# Power.net
KiCad netlist of a schematic drawn in Altium Designer
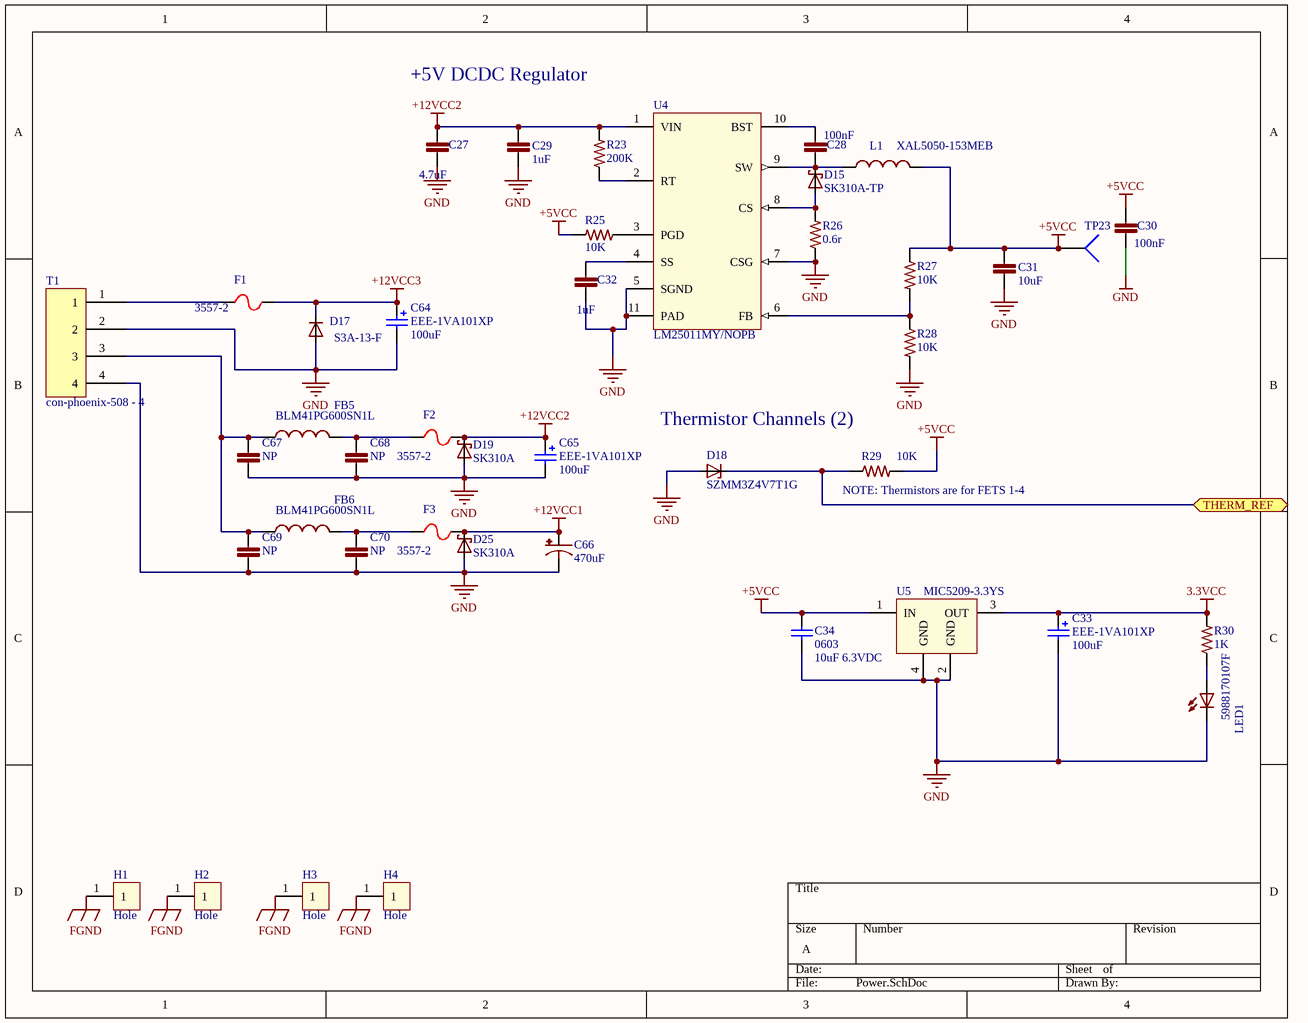
[diagram p0: Power.SchDoc]

(export (version "E")
  (design (tool "Eeschema 10.0.6"))
  (components
    (comp (ref "C27")
      (value "4.7uF")
      (footprint "C1206")
      (description "CAP CER 1206 4.7uF 50V 10% X5R")
      (fields
        (field (name "MANUFACTURERPARTNUMBER") "C1206C475K5PACTU")
        (field (name "PUBLISHER") "UltiMachine")
      )
      (libsource (lib "3Delight") (part "C1206C475K5PACTU"))
    )
    (comp (ref "C28")
      (value "100nF")
      (footprint "C0603")
      (description "CAP CER 0603 100nF 50V 10% X7R")
      (fields
        (field (name "MANUFACTURERPARTNUMBER") "C0603C104K5RACTU")
        (field (name "PUBLISHER") "UltiMachine")
      )
      (libsource (lib "3Delight") (part "C0603C104K5RACTU"))
    )
    (comp (ref "C29")
      (value "1uF")
      (footprint "C0805")
      (description "CAP CER 0805 1uF 50V 10% X7R")
      (fields
        (field (name "MANUFACTURERPARTNUMBER") "GRM21BR71H105KA12L")
        (field (name "PUBLISHER") "UltiMachine")
      )
      (libsource (lib "3Delight") (part "GRM21BR71H105KA12L"))
    )
    (comp (ref "C30")
      (value "100nF")
      (footprint "C0603")
      (description "CAP CER 0603 100nF 50V 10% X7R")
      (fields
        (field (name "MANUFACTURERPARTNUMBER") "C0603C104K5RACTU")
        (field (name "PUBLISHER") "UltiMachine")
      )
      (libsource (lib "3Delight") (part "C0603C104K5RACTU"))
    )
    (comp (ref "C31")
      (value "10uF")
      (footprint "C0805")
      (description "CAP CER 0805 10uF 10V 10% X5R")
      (fields
        (field (name "MANUFACTURERPARTNUMBER") "C0805C106K8PACTU")
        (field (name "PUBLISHER") "UltiMachine")
      )
      (libsource (lib "3Delight") (part "C0805C106K8PACTU"))
    )
    (comp (ref "C32")
      (value "1uF")
      (footprint "C0402")
      (description "CAP CER 0402 1uF 6.3V 10% X5R")
      (fields
        (field (name "MANUFACTURERPARTNUMBER") "GRM155R60J105KE19D")
        (field (name "PUBLISHER") "UltiMachine")
      )
      (libsource (lib "3Delight") (part "GRM155R60J105KE19D"))
    )
    (comp (ref "C33")
      (value "EEE-1VA101XP")
      (footprint "EEE-1VA101XP")
      (description "CAP ALUM 100UF 35V 20% SMD")
      (fields (field (name "DIGIKEY PART #") "PCE3951CT-ND") (field (name "ALTIUM_VALUE") "100uF"))
      (libsource (lib "Tigershark3D") (part "EEE-1VA101XP"))
    )
    (comp (ref "C34")
      (value "0603")
      (footprint "C0603")
      (description "CAP CER 10UF 6.3V 10% JB 0603")
      (fields
        (field (name "MFR PART #") "C1608JB0J106K080AB")
        (field (name "MFR") "TDK")
        (field (name "ALTIUM_VALUE") "10uF 6.3VDC")
      )
      (libsource (lib "Tigershark3D") (part "C1608JB0J106K080AB"))
    )
    (comp (ref "C64")
      (value "EEE-1VA101XP")
      (footprint "EEE-1VA101XP")
      (description "CAP ALUM 100UF 35V 20% SMD")
      (fields (field (name "DIGIKEY PART #") "PCE3951CT-ND") (field (name "ALTIUM_VALUE") "100uF"))
      (libsource (lib "Tigershark3D") (part "EEE-1VA101XP"))
    )
    (comp (ref "C65")
      (value "EEE-1VA101XP")
      (footprint "EEE-1VA101XP")
      (description "CAP ALUM 100UF 35V 20% SMD")
      (fields (field (name "DIGIKEY PART #") "PCE3951CT-ND") (field (name "ALTIUM_VALUE") "100uF"))
      (libsource (lib "Tigershark3D") (part "EEE-1VA101XP"))
    )
    (comp (ref "C66")
      (value "470uF")
      (footprint "C12,5-5")
      (description "CAP ALU 470uF 50V 20%")
      (fields
        (field (name "MANUFACTURERPARTNUMBER") "UPW1H471MHD1TO")
        (field (name "PUBLISHER") "UltiMachine")
      )
      (libsource (lib "Tigershark3D") (part "UPW1H471MHD1TO"))
    )
    (comp (ref "C67")
      (value "NP")
      (footprint "C0603")
      (description "CAP CER 0603 100nF 50V 10% X7R")
      (fields
        (field (name "MANUFACTURERPARTNUMBER") "C0603C104K5RACTU")
        (field (name "PUBLISHER") "UltiMachine")
      )
      (libsource (lib "3Delight") (part "C0603C104K5RACTU"))
    )
    (comp (ref "C68")
      (value "NP")
      (footprint "C0603")
      (description "CAP CER 0603 100nF 50V 10% X7R")
      (fields
        (field (name "MANUFACTURERPARTNUMBER") "C0603C104K5RACTU")
        (field (name "PUBLISHER") "UltiMachine")
      )
      (libsource (lib "3Delight") (part "C0603C104K5RACTU"))
    )
    (comp (ref "C69")
      (value "NP")
      (footprint "C0603")
      (description "CAP CER 0603 100nF 50V 10% X7R")
      (fields
        (field (name "MANUFACTURERPARTNUMBER") "C0603C104K5RACTU")
        (field (name "PUBLISHER") "UltiMachine")
      )
      (libsource (lib "3Delight") (part "C0603C104K5RACTU"))
    )
    (comp (ref "C70")
      (value "NP")
      (footprint "C0603")
      (description "CAP CER 0603 100nF 50V 10% X7R")
      (fields
        (field (name "MANUFACTURERPARTNUMBER") "C0603C104K5RACTU")
        (field (name "PUBLISHER") "UltiMachine")
      )
      (libsource (lib "3Delight") (part "C0603C104K5RACTU"))
    )
    (comp (ref "D15")
      (value "SK310A-TP")
      (footprint "SMA-SM")
      (description "DIODE Schottky 3A SMA")
      (fields (field (name "MANUFACTURERPARTNUMBER") "SK310A") (field (name "PUBLISHER") "UltiMachine"))
      (libsource (lib "3Delight") (part "SK310A"))
    )
    (comp (ref "D17")
      (value "S3A-13-F")
      (footprint "DO-214AB")
      (description "DIODE DO-214AB")
      (fields (field (name "PUBLISHER") "UltiMachine"))
      (libsource (lib "3Delight") (part "S3A-13-F"))
    )
    (comp (ref "D18")
      (value "SZMM3Z4V7T1G")
      (footprint "SOD323-R")
      (description "Z-Diode")
      (fields (field (name "MANUFACTURER") "Fairchild") (field (name "PUBLISHER") "UltiMachine"))
      (libsource (lib "Tigershark3D") (part "SZMM3Z4V7T1G"))
    )
    (comp (ref "D19")
      (value "SK310A")
      (footprint "SMA-SM")
      (description "DIODE Schottky 3A SMA")
      (fields (field (name "PUBLISHER") "UltiMachine"))
      (libsource (lib "3Delight") (part "SK310A"))
    )
    (comp (ref "D25")
      (value "SK310A")
      (footprint "SMA-SM")
      (description "DIODE Schottky 3A SMA")
      (fields (field (name "PUBLISHER") "UltiMachine"))
      (libsource (lib "3Delight") (part "SK310A"))
    )
    (comp (ref "F1")
      (value "3557-2")
      (footprint "3557")
      (description "FUSE PTH ATO")
      (fields (field (name "PUBLISHER") "UltiMachine"))
      (libsource (lib "3Delight") (part "3557-2"))
    )
    (comp (ref "F2")
      (value "3557-2")
      (footprint "3557")
      (description "FUSE PTH ATO")
      (fields (field (name "PUBLISHER") "UltiMachine"))
      (libsource (lib "3Delight") (part "3557-2"))
    )
    (comp (ref "F3")
      (value "3557-2")
      (footprint "3557")
      (description "FUSE PTH ATO")
      (fields (field (name "PUBLISHER") "UltiMachine"))
      (libsource (lib "3Delight") (part "3557-2"))
    )
    (comp (ref "FB5")
      (value "BLM41PG600SN1L")
      (footprint "L1806")
      (description "FERRITE BEAD 1806 60ohm")
      (fields (field (name "PUBLISHER") "UltiMachine"))
      (libsource (lib "3Delight") (part "BLM41PG600SN1L"))
    )
    (comp (ref "FB6")
      (value "BLM41PG600SN1L")
      (footprint "L1806")
      (description "FERRITE BEAD 1806 60ohm")
      (fields (field (name "PUBLISHER") "UltiMachine"))
      (libsource (lib "3Delight") (part "BLM41PG600SN1L"))
    )
    (comp (ref "H1")
      (value "Hole")
      (footprint "Wave_hole_3x7-singleSided")
      (libsource (lib "3Delight") (part "Hole"))
    )
    (comp (ref "H2")
      (value "Hole")
      (footprint "Wave_hole_3x7-singleSided")
      (libsource (lib "3Delight") (part "Hole"))
    )
    (comp (ref "H3")
      (value "Hole")
      (footprint "Wave_hole_3x7-singleSided")
      (libsource (lib "3Delight") (part "Hole"))
    )
    (comp (ref "H4")
      (value "Hole")
      (footprint "Wave_hole_3x7-singleSided")
      (libsource (lib "3Delight") (part "Hole"))
    )
    (comp (ref "L1")
      (value "XAL5050-153MEB")
      (footprint "XAL50xx-153")
      (description "IND 15uH 3.9A 20%")
      (fields (field (name "PUBLISHER") "UltiMachine"))
      (libsource (lib "3Delight") (part "XAL5050-153MEB"))
    )
    (comp (ref "LED1")
      (value "5988170107F")
      (footprint "LED2012120")
      (description "LED 0805 Green")
      (fields (field (name "PUBLISHER") "UltiMachine"))
      (libsource (lib "3Delight") (part "5988170107F"))
    )
    (comp (ref "R23")
      (value "200K")
      (footprint "R0402")
      (description "RES 0402 22r 63mW 1%")
      (fields
        (field (name "MANUFACTURERPARTNUMBER") "CRCW0402200KFKED")
        (field (name "PUBLISHER") "UltiMachine")
      )
      (libsource (lib "3Delight") (part "CRCW0402200KFKED"))
    )
    (comp (ref "R25")
      (value "10K")
      (footprint "R0603")
      (description "RES 0603 10K 100mW 1%")
      (fields
        (field (name "MANUFACTURERPARTNUMBER") "ERJ-3EKF1002V")
        (field (name "PUBLISHER") "UltiMachine")
      )
      (libsource (lib "3Delight") (part "ERJ-3EKF1002V"))
    )
    (comp (ref "R26")
      (value "0.6r")
      (footprint "2512R-0.55")
      (description "RES 0.06 OHM 1W 1% 2512 SMD")
      (fields
        (field (name "MANUFACTURERPARTNUMBER") "RL2512FK-070R06L")
        (field (name "PUBLISHER") "UltiMachine")
      )
      (libsource (lib "3Delight") (part "RL2512FK-070R06L"))
    )
    (comp (ref "R27")
      (value "10K")
      (footprint "R0603")
      (description "RES 0603 10K 100mW 1%")
      (fields
        (field (name "MANUFACTURERPARTNUMBER") "ERJ-3EKF1002V")
        (field (name "PUBLISHER") "UltiMachine")
      )
      (libsource (lib "3Delight") (part "ERJ-3EKF1002V"))
    )
    (comp (ref "R28")
      (value "10K")
      (footprint "R0603")
      (description "RES 0603 10K 100mW 1%")
      (fields
        (field (name "MANUFACTURERPARTNUMBER") "ERJ-3EKF1002V")
        (field (name "PUBLISHER") "UltiMachine")
      )
      (libsource (lib "3Delight") (part "ERJ-3EKF1002V"))
    )
    (comp (ref "R29")
      (value "10K")
      (footprint "R0603")
      (description "RES 0603 10K 100mW 1%")
      (fields
        (field (name "MANUFACTURERPARTNUMBER") "ERJ-3EKF1002V")
        (field (name "PUBLISHER") "UltiMachine")
      )
      (libsource (lib "3Delight") (part "ERJ-3EKF1002V"))
    )
    (comp (ref "R30")
      (value "1K")
      (footprint "R0603")
      (description "RES 0603 1K 100mW 1%")
      (fields
        (field (name "MANUFACTURERPARTNUMBER") "ERJ-3EKF1001V")
        (field (name "PUBLISHER") "UltiMachine")
      )
      (libsource (lib "Tigershark3D") (part "ERJ-3EKF1001V"))
    )
    (comp (ref "T1")
      (value "con-phoenix-508 - 4")
      (footprint "MSTBV4")
      (libsource (lib "ZMBo Schematic Library") (part "con-phoenix-508_4"))
    )
    (comp (ref "TP23")
      (value "TP4")
      (footprint "TP-2")
      (description "Socket")
      (fields (field (name "PUBLISHER") "Altium Limited"))
      (libsource (lib "ZMBo Schematic Library") (part "Socket"))
    )
    (comp (ref "U4")
      (value "LM25011MY/NOPB")
      (footprint "VSSOP10")
      (description "REG BUCK")
      (libsource (lib "3Delight") (part "LM25011"))
    )
    (comp (ref "U5")
      (value "MIC5209-3.3YS")
      (footprint "SOT230P700X190-4N")
      (libsource (lib "3Delight") (part "MIC5209-3.3YS"))
    )
  )
  (nets
    (net (code "1") (name "+5VCC") (class "Default")
      (node (ref "C30") (pin "1") (pinfunction "1_1") (pintype "passive"))
      (node (ref "C31") (pin "1") (pinfunction "1_1") (pintype "passive"))
      (node (ref "C34") (pin "2") (pinfunction "2_2") (pintype "passive"))
      (node (ref "L1") (pin "2") (pinfunction "2_2") (pintype "passive"))
      (node (ref "R25") (pin "2") (pinfunction "2_2") (pintype "passive"))
      (node (ref "R27") (pin "1") (pinfunction "1_1") (pintype "passive"))
      (node (ref "R29") (pin "2") (pinfunction "2_2") (pintype "passive"))
      (node (ref "TP23") (pin "1") (pinfunction "1_1") (pintype "passive"))
      (node (ref "U5") (pin "1") (pinfunction "IN_1") (pintype "power_in"))
    )
    (net (code "2") (name "+12VCC1") (class "Default")
      (node (ref "C66") (pin "1") (pinfunction "+_1") (pintype "passive"))
      (node (ref "D25") (pin "C") (pinfunction "C_C") (pintype "passive"))
      (node (ref "F3") (pin "2") (pinfunction "2_2") (pintype "passive"))
    )
    (net (code "3") (name "+12VCC2") (class "Default")
      (node (ref "C27") (pin "1") (pinfunction "1_1") (pintype "passive"))
      (node (ref "C29") (pin "1") (pinfunction "1_1") (pintype "passive"))
      (node (ref "C65") (pin "1") (pinfunction "1_1") (pintype "passive"))
      (node (ref "D19") (pin "C") (pinfunction "C_C") (pintype "passive"))
      (node (ref "F2") (pin "2") (pinfunction "2_2") (pintype "passive"))
      (node (ref "R23") (pin "2") (pinfunction "2_2") (pintype "passive"))
      (node (ref "U4") (pin "1") (pinfunction "VIN_1") (pintype "power_in"))
    )
    (net (code "4") (name "+12VCC3") (class "Default")
      (node (ref "C64") (pin "1") (pinfunction "1_1") (pintype "passive"))
      (node (ref "D17") (pin "C") (pinfunction "C_C") (pintype "passive"))
      (node (ref "F1") (pin "2") (pinfunction "2_2") (pintype "passive"))
    )
    (net (code "5") (name "/THERM_REF") (class "Default")
      (node (ref "D18") (pin "C") (pinfunction "C_C") (pintype "passive"))
      (node (ref "R29") (pin "1") (pinfunction "1_1") (pintype "passive"))
    )
    (net (code "6") (name "3.3VCC") (class "Default")
      (node (ref "C33") (pin "1") (pinfunction "1_1") (pintype "passive"))
      (node (ref "R30") (pin "2") (pinfunction "2_2") (pintype "passive"))
      (node (ref "U5") (pin "3") (pinfunction "OUT_3") (pintype "power_in"))
    )
    (net (code "7") (name "FGND") (class "Default")
      (node (ref "H1") (pin "1") (pinfunction "1_1") (pintype "power_in"))
      (node (ref "H2") (pin "1") (pinfunction "1_1") (pintype "power_in"))
      (node (ref "H3") (pin "1") (pinfunction "1_1") (pintype "power_in"))
      (node (ref "H4") (pin "1") (pinfunction "1_1") (pintype "power_in"))
    )
    (net (code "8") (name "GND") (class "Default")
      (node (ref "C27") (pin "2") (pinfunction "2_2") (pintype "passive"))
      (node (ref "C29") (pin "2") (pinfunction "2_2") (pintype "passive"))
      (node (ref "C30") (pin "2") (pinfunction "2_2") (pintype "passive"))
      (node (ref "C31") (pin "2") (pinfunction "2_2") (pintype "passive"))
      (node (ref "C32") (pin "2") (pinfunction "2_2") (pintype "passive"))
      (node (ref "C33") (pin "2") (pinfunction "2_2") (pintype "passive"))
      (node (ref "C34") (pin "1") (pinfunction "1_1") (pintype "passive"))
      (node (ref "C64") (pin "2") (pinfunction "2_2") (pintype "passive"))
      (node (ref "C65") (pin "2") (pinfunction "2_2") (pintype "passive"))
      (node (ref "C66") (pin "2") (pinfunction "-_2") (pintype "passive"))
      (node (ref "C67") (pin "2") (pinfunction "2_2") (pintype "passive"))
      (node (ref "C68") (pin "2") (pinfunction "2_2") (pintype "passive"))
      (node (ref "C69") (pin "2") (pinfunction "2_2") (pintype "passive"))
      (node (ref "C70") (pin "2") (pinfunction "2_2") (pintype "passive"))
      (node (ref "D17") (pin "A") (pinfunction "A_A") (pintype "passive"))
      (node (ref "D18") (pin "A") (pinfunction "A_A") (pintype "passive"))
      (node (ref "D19") (pin "A") (pinfunction "A_A") (pintype "passive"))
      (node (ref "D25") (pin "A") (pinfunction "A_A") (pintype "passive"))
      (node (ref "LED1") (pin "C") (pinfunction "C_C") (pintype "passive"))
      (node (ref "R26") (pin "1") (pinfunction "1_1") (pintype "passive"))
      (node (ref "R28") (pin "2") (pinfunction "2_2") (pintype "passive"))
      (node (ref "T1") (pin "2") (pinfunction "2_2") (pintype "passive"))
      (node (ref "T1") (pin "4") (pinfunction "4_4") (pintype "passive"))
      (node (ref "U4") (pin "11") (pinfunction "PAD_11") (pintype "power_in"))
      (node (ref "U4") (pin "5") (pinfunction "SGND_5") (pintype "power_in"))
      (node (ref "U4") (pin "7") (pinfunction "CSG_7") (pintype "input"))
      (node (ref "U5") (pin "2") (pinfunction "GND_2") (pintype "power_in"))
      (node (ref "U5") (pin "4") (pinfunction "GND_4") (pintype "power_in"))
    )
    (net (code "9") (name "Net-(C67-Pad1)") (class "Default")
      (node (ref "C67") (pin "1") (pinfunction "1_1") (pintype "passive"))
      (node (ref "C69") (pin "1") (pinfunction "1_1") (pintype "passive"))
      (node (ref "FB5") (pin "1") (pinfunction "1_1") (pintype "passive"))
      (node (ref "FB6") (pin "1") (pinfunction "1_1") (pintype "passive"))
      (node (ref "T1") (pin "3") (pinfunction "3_3") (pintype "passive"))
    )
    (net (code "10") (name "Net-(C68-Pad1)") (class "Default")
      (node (ref "C68") (pin "1") (pinfunction "1_1") (pintype "passive"))
      (node (ref "F2") (pin "1") (pinfunction "1_1") (pintype "passive"))
      (node (ref "FB5") (pin "2") (pinfunction "2_2") (pintype "passive"))
    )
    (net (code "11") (name "Net-(C70-Pad1)") (class "Default")
      (node (ref "C70") (pin "1") (pinfunction "1_1") (pintype "passive"))
      (node (ref "F3") (pin "1") (pinfunction "1_1") (pintype "passive"))
      (node (ref "FB6") (pin "2") (pinfunction "2_2") (pintype "passive"))
    )
    (net (code "12") (name "Net-(F1-Pad1)") (class "Default")
      (node (ref "F1") (pin "1") (pinfunction "1_1") (pintype "passive"))
      (node (ref "T1") (pin "1") (pinfunction "1_1") (pintype "passive"))
    )
    (net (code "13") (name "Net-(LED1-PadA)") (class "Default")
      (node (ref "LED1") (pin "A") (pinfunction "A_A") (pintype "passive"))
      (node (ref "R30") (pin "1") (pinfunction "1_1") (pintype "passive"))
    )
    (net (code "14") (name "Net-(U4-BST)") (class "Default")
      (node (ref "C28") (pin "1") (pinfunction "1_1") (pintype "passive"))
      (node (ref "U4") (pin "10") (pinfunction "BST_10") (pintype "power_in"))
    )
    (net (code "15") (name "Net-(U4-CS)") (class "Default")
      (node (ref "D15") (pin "A") (pinfunction "A_A") (pintype "passive"))
      (node (ref "R26") (pin "2") (pinfunction "2_2") (pintype "passive"))
      (node (ref "U4") (pin "8") (pinfunction "CS_8") (pintype "input"))
    )
    (net (code "16") (name "Net-(U4-FB)") (class "Default")
      (node (ref "R27") (pin "2") (pinfunction "2_2") (pintype "passive"))
      (node (ref "R28") (pin "1") (pinfunction "1_1") (pintype "passive"))
      (node (ref "U4") (pin "6") (pinfunction "FB_6") (pintype "input"))
    )
    (net (code "17") (name "Net-(U4-PGD)") (class "Default")
      (node (ref "R25") (pin "1") (pinfunction "1_1") (pintype "passive"))
      (node (ref "U4") (pin "3") (pinfunction "PGD_3") (pintype "power_in"))
    )
    (net (code "18") (name "Net-(U4-RT)") (class "Default")
      (node (ref "R23") (pin "1") (pinfunction "1_1") (pintype "passive"))
      (node (ref "U4") (pin "2") (pinfunction "RT_2") (pintype "power_in"))
    )
    (net (code "19") (name "Net-(U4-SS)") (class "Default")
      (node (ref "C32") (pin "1") (pinfunction "1_1") (pintype "passive"))
      (node (ref "U4") (pin "4") (pinfunction "SS_4") (pintype "power_in"))
    )
    (net (code "20") (name "Net-(U4-SW)") (class "Default")
      (node (ref "C28") (pin "2") (pinfunction "2_2") (pintype "passive"))
      (node (ref "D15") (pin "C") (pinfunction "C_C") (pintype "passive"))
      (node (ref "L1") (pin "1") (pinfunction "1_1") (pintype "passive"))
      (node (ref "U4") (pin "9") (pinfunction "SW_9") (pintype "output"))
    )
  )
)
